# G_Humi_v2_SCH.net
KiCad netlist of a schematic drawn in Altium Designer
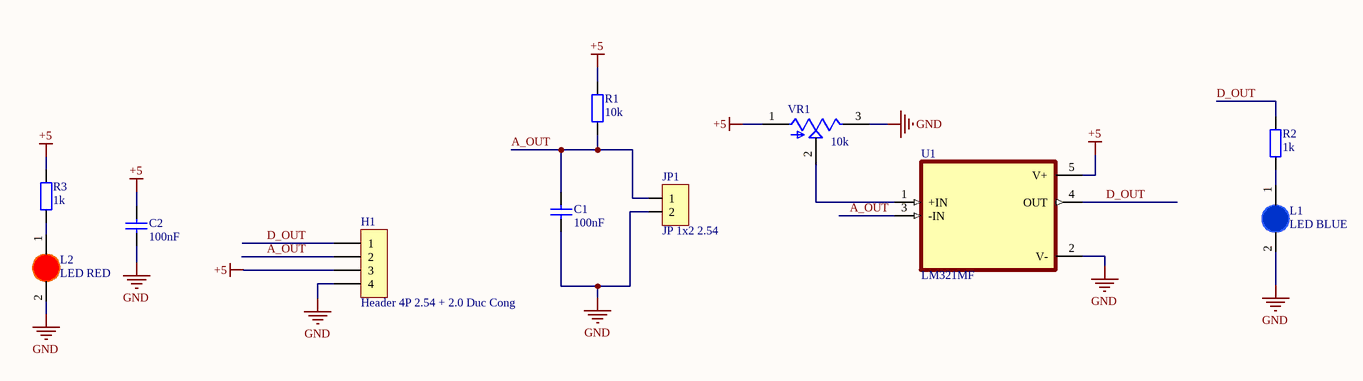
[diagram p0: G_Humi_v2_SCH.SchDoc]

(export (version "E")
  (design (tool "Eeschema 10.0.6"))
  (components
    (comp (ref "C1")
      (value "100nF")
      (footprint "tu 0603")
      (description "Dán")
      (libsource (lib "namnt_Lib") (part "Tu 0603 104 50V 10%"))
    )
    (comp (ref "C2")
      (value "100nF")
      (footprint "tu 0603")
      (description "Dán")
      (libsource (lib "namnt_Lib") (part "Tu 0603 104 50V 10%"))
    )
    (comp (ref "H1")
      (value "Header 4P 2.54 + 2.0 Duc Cong")
      (footprint "Header 4P DC 2.54 + 2.0")
      (description "Cắm")
      (libsource (lib "namnt_Lib") (part "Header 4P 2.54 + 2.0 Duc Cong"))
    )
    (comp (ref "JP1")
      (value "JP 1x2 2.54")
      (footprint "JP 1x2 DC")
      (description "Cắm")
      (libsource (lib "namnt_Lib") (part "JP 1x2 2.54 Duc Cong"))
    )
    (comp (ref "L1")
      (value "LED BLUE")
      (footprint "LED-0805-Blue")
      (description "Dán")
      (libsource (lib "namnt_Lib") (part "LED 0805 Xanh Duong"))
    )
    (comp (ref "L2")
      (value "LED RED")
      (footprint "LED-0805-Red")
      (description "Dán")
      (libsource (lib "namnt_Lib") (part "LED 0805 Do"))
    )
    (comp (ref "R1")
      (value "10k")
      (footprint "tro smd 0603")
      (description "Dán")
      (libsource (lib "namnt_Lib") (part "Tro 0603 1% 10k"))
    )
    (comp (ref "R2")
      (value "1k")
      (footprint "tro smd 0603")
      (description "Dán")
      (libsource (lib "namnt_Lib") (part "Tro 0603 1% 1k"))
    )
    (comp (ref "R3")
      (value "1k")
      (footprint "tro smd 0603")
      (description "Dán")
      (libsource (lib "namnt_Lib") (part "Tro 0603 1% 1k"))
    )
    (comp (ref "U1")
      (value "LM321MF")
      (footprint "SOT95P280X145-5N")
      (description "Low Power Single Op Amp 5-SOT-23 -40 to 85")
      (fields (field (name "MF") "Texas Instruments"))
      (libsource (lib "namnt_Lib") (part "LM321MF"))
    )
    (comp (ref "VR1")
      (value "10k")
      (footprint "TRIM_3362P-1-102")
      (description "TRIMMER - 1/4in SQ ST CERMET ¦ Bourns 3362P-1-102")
      (fields (field (name "MF") "Bourns") (field (name "MP") "3362P-1-102"))
      (libsource (lib "namnt_Lib") (part "Bien tro vuong"))
    )
  )
  (nets
    (net (code "1") (name "+5") (class "Default")
      (node (ref "C2") (pin "1") (pinfunction "1_1") (pintype "passive"))
      (node (ref "H1") (pin "3") (pinfunction "3_3") (pintype "passive"))
      (node (ref "R1") (pin "2") (pinfunction "2_2") (pintype "passive"))
      (node (ref "R3") (pin "2") (pinfunction "2_2") (pintype "passive"))
      (node (ref "U1") (pin "5") (pinfunction "V+_5") (pintype "power_in"))
      (node (ref "VR1") (pin "1") (pinfunction "CCW_1") (pintype "passive"))
    )
    (net (code "2") (name "/A_OUT") (class "Default")
      (node (ref "C1") (pin "1") (pinfunction "1_1") (pintype "passive"))
      (node (ref "H1") (pin "2") (pinfunction "2_2") (pintype "passive"))
      (node (ref "JP1") (pin "1") (pinfunction "1_1") (pintype "passive"))
      (node (ref "R1") (pin "1") (pinfunction "1_1") (pintype "passive"))
      (node (ref "U1") (pin "3") (pinfunction "-IN_3") (pintype "input"))
    )
    (net (code "3") (name "/D_OUT") (class "Default")
      (node (ref "H1") (pin "1") (pinfunction "1_1") (pintype "passive"))
      (node (ref "R2") (pin "2") (pinfunction "2_2") (pintype "passive"))
      (node (ref "U1") (pin "4") (pinfunction "OUT_4") (pintype "output"))
    )
    (net (code "4") (name "GND") (class "Default")
      (node (ref "C1") (pin "2") (pinfunction "2_2") (pintype "passive"))
      (node (ref "C2") (pin "2") (pinfunction "2_2") (pintype "passive"))
      (node (ref "H1") (pin "4") (pinfunction "4_4") (pintype "passive"))
      (node (ref "JP1") (pin "2") (pinfunction "2_2") (pintype "passive"))
      (node (ref "L1") (pin "2") (pinfunction "K_2") (pintype "passive"))
      (node (ref "L2") (pin "2") (pinfunction "K_2") (pintype "passive"))
      (node (ref "U1") (pin "2") (pinfunction "V-_2") (pintype "power_in"))
      (node (ref "VR1") (pin "3") (pinfunction "CW_3") (pintype "passive"))
    )
    (net (code "5") (name "Net-(L1-A)") (class "Default")
      (node (ref "L1") (pin "1") (pinfunction "A_1") (pintype "passive"))
      (node (ref "R2") (pin "1") (pinfunction "1_1") (pintype "passive"))
    )
    (net (code "6") (name "Net-(L2-A)") (class "Default")
      (node (ref "L2") (pin "1") (pinfunction "A_1") (pintype "passive"))
      (node (ref "R3") (pin "1") (pinfunction "1_1") (pintype "passive"))
    )
    (net (code "7") (name "Net-(U1-+IN)") (class "Default")
      (node (ref "U1") (pin "1") (pinfunction "+IN_1") (pintype "input"))
      (node (ref "VR1") (pin "2") (pinfunction "WIPER_2") (pintype "passive"))
    )
  )
)
